# SSFocuser-C-DRV8825.net
KiCad netlist of a schematic drawn in Altium Designer
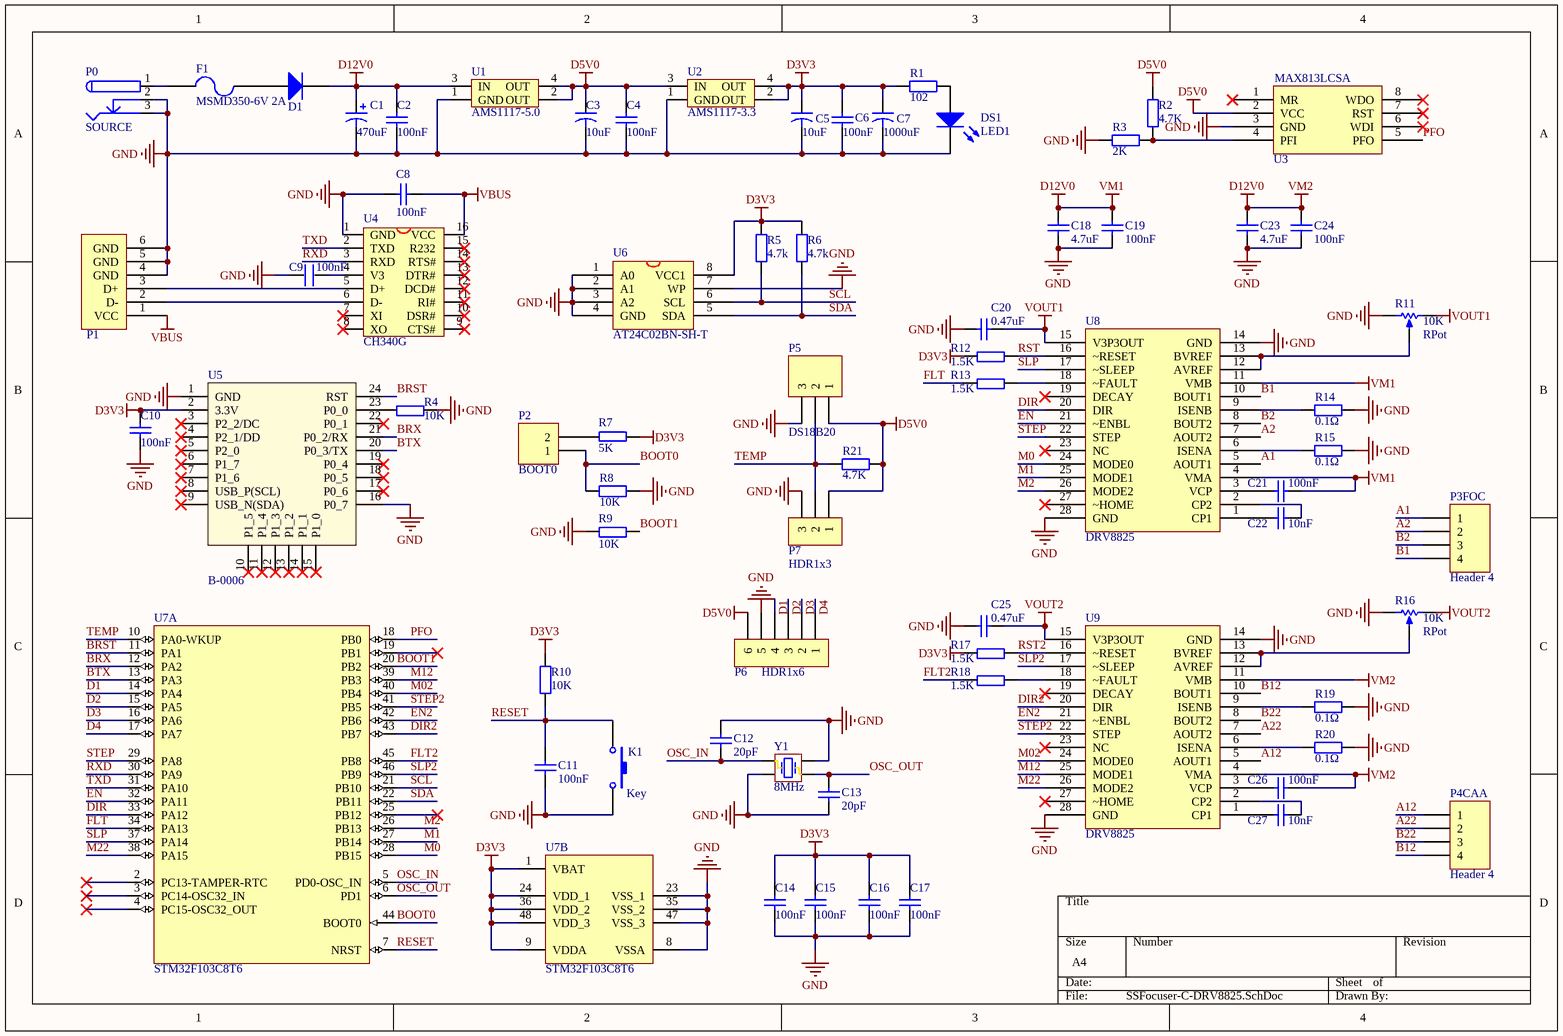
[diagram p0: SSFocuser-C-DRV8825.SchDoc]

(export (version "E")
  (design (tool "Eeschema 10.0.6"))
  (components
    (comp (ref "C1")
      (value "470uF")
      (footprint "16V/470U(CD10X10D5)")
      (description "470UF      16V      CD10X10D5")
      (libsource (lib "平台原理图symbol图库V1.0") (part "C470UF016S"))
    )
    (comp (ref "C2")
      (value "100nF")
      (footprint "0603C")
      (description "Capacitor")
      (fields (field (name "PUBLISHER") "Altium Limited"))
      (libsource (lib "Crazy_PCB") (part "Cap"))
    )
    (comp (ref "C3")
      (value "10uF")
      (footprint "3216")
      (fields (field (name "VAULE") "10uF"))
      (libsource (lib "Crazy_PCB") (part "CAP2"))
    )
    (comp (ref "C4")
      (value "100nF")
      (footprint "0603C")
      (description "Capacitor")
      (fields (field (name "PUBLISHER") "Altium Limited"))
      (libsource (lib "Crazy_PCB") (part "Cap"))
    )
    (comp (ref "C5")
      (value "10uF")
      (footprint "3216")
      (fields (field (name "VAULE") "10uF"))
      (libsource (lib "Crazy_PCB") (part "CAP2"))
    )
    (comp (ref "C6")
      (value "100nF")
      (footprint "0603C")
      (description "Capacitor")
      (fields (field (name "PUBLISHER") "Altium Limited"))
      (libsource (lib "Crazy_PCB") (part "Cap"))
    )
    (comp (ref "C7")
      (value "1000uF")
      (footprint "16V/470U(CD10X10D5)")
      (fields (field (name "VAULE") "1000uF"))
      (libsource (lib "Crazy_PCB") (part "CAP2"))
    )
    (comp (ref "C8")
      (value "100nF")
      (footprint "0603C")
      (description "Capacitor")
      (fields (field (name "PUBLISHER") "Altium Limited"))
      (libsource (lib "Crazy_PCB") (part "Cap"))
    )
    (comp (ref "C9")
      (value "100nF")
      (footprint "0603C")
      (libsource (lib "WarShip V3 STM32103封装库") (part "C"))
    )
    (comp (ref "C10")
      (value "100nF")
      (footprint "0603C")
      (description "Capacitor")
      (fields (field (name "PUBLISHER") "Altium Limited"))
      (libsource (lib "Crazy_PCB") (part "Cap"))
    )
    (comp (ref "C11")
      (value "100nF")
      (footprint "0603C")
      (description "Capacitor")
      (fields (field (name "PUBLISHER") "Altium Limited"))
      (libsource (lib "Crazy_PCB") (part "Cap"))
    )
    (comp (ref "C12")
      (value "20pF")
      (footprint "0603C")
      (description "Capacitor")
      (fields (field (name "PUBLISHER") "Altium Limited"))
      (libsource (lib "JL_SCH") (part "Cap"))
    )
    (comp (ref "C13")
      (value "20pF")
      (footprint "0603C")
      (description "Capacitor")
      (fields (field (name "PUBLISHER") "Altium Limited"))
      (libsource (lib "JL_SCH") (part "Cap"))
    )
    (comp (ref "C14")
      (value "100nF")
      (footprint "0603C")
      (description "Capacitor")
      (fields (field (name "PUBLISHER") "Altium Limited"))
      (libsource (lib "Crazy_PCB") (part "Cap"))
    )
    (comp (ref "C15")
      (value "100nF")
      (footprint "0603C")
      (description "Capacitor")
      (fields (field (name "PUBLISHER") "Altium Limited"))
      (libsource (lib "Crazy_PCB") (part "Cap"))
    )
    (comp (ref "C16")
      (value "100nF")
      (footprint "0603C")
      (description "Capacitor")
      (fields (field (name "PUBLISHER") "Altium Limited"))
      (libsource (lib "Crazy_PCB") (part "Cap"))
    )
    (comp (ref "C17")
      (value "100nF")
      (footprint "0603C")
      (description "Capacitor")
      (fields (field (name "PUBLISHER") "Altium Limited"))
      (libsource (lib "Crazy_PCB") (part "Cap"))
    )
    (comp (ref "C18")
      (value "4.7uF")
      (footprint "1206C")
      (description "Capacitor")
      (fields (field (name "PUBLISHER") "Altium Limited"))
      (libsource (lib "Crazy_PCB") (part "Cap"))
    )
    (comp (ref "C19")
      (value "100nF")
      (footprint "0603C")
      (description "Capacitor")
      (fields (field (name "PUBLISHER") "Altium Limited"))
      (libsource (lib "Crazy_PCB") (part "Cap"))
    )
    (comp (ref "C20")
      (value "0.47uF")
      (footprint "0603C")
      (description "Capacitor")
      (fields (field (name "PUBLISHER") "Altium Limited"))
      (libsource (lib "Crazy_PCB") (part "Cap"))
    )
    (comp (ref "C21")
      (value "100nF")
      (footprint "0603C")
      (description "Capacitor")
      (fields (field (name "PUBLISHER") "Altium Limited"))
      (libsource (lib "Crazy_PCB") (part "Cap"))
    )
    (comp (ref "C22")
      (value "10nF")
      (footprint "0603C")
      (description "Capacitor")
      (fields (field (name "PUBLISHER") "Altium Limited"))
      (libsource (lib "Crazy_PCB") (part "Cap"))
    )
    (comp (ref "C23")
      (value "4.7uF")
      (footprint "1206C")
      (description "Capacitor")
      (fields (field (name "PUBLISHER") "Altium Limited"))
      (libsource (lib "Crazy_PCB") (part "Cap"))
    )
    (comp (ref "C24")
      (value "100nF")
      (footprint "0603C")
      (description "Capacitor")
      (fields (field (name "PUBLISHER") "Altium Limited"))
      (libsource (lib "Crazy_PCB") (part "Cap"))
    )
    (comp (ref "C25")
      (value "0.47uF")
      (footprint "0603C")
      (description "Capacitor")
      (fields (field (name "PUBLISHER") "Altium Limited"))
      (libsource (lib "Crazy_PCB") (part "Cap"))
    )
    (comp (ref "C26")
      (value "100nF")
      (footprint "0603C")
      (description "Capacitor")
      (fields (field (name "PUBLISHER") "Altium Limited"))
      (libsource (lib "Crazy_PCB") (part "Cap"))
    )
    (comp (ref "C27")
      (value "10nF")
      (footprint "0603C")
      (description "Capacitor")
      (fields (field (name "PUBLISHER") "Altium Limited"))
      (libsource (lib "Crazy_PCB") (part "Cap"))
    )
    (comp (ref "D1")
      (value "M7")
      (footprint "DO-214AC")
      (description "High Conductance Fast Diode")
      (fields (field (name "PUBLISHER") "Altium Limited"))
      (libsource (lib "Crazy_PCB") (part "Diode"))
    )
    (comp (ref "DS1")
      (value "LED1")
      (footprint "0805D")
      (description "Typical RED, GREEN, YELLOW, AMBER GaAs LED")
      (fields (field (name "PUBLISHER") "Altium Limited"))
      (libsource (lib "MiniSTM32 V3.0封装库") (part "LED2"))
    )
    (comp (ref "F1")
      (value "MSMD350-6V 2A")
      (footprint "1812R")
      (description "Fuse")
      (libsource (lib "JL_SCH") (part "FUSE2"))
    )
    (comp (ref "K1")
      (value "Key")
      (footprint "SW-4*6")
      (description "Switch")
      (fields (field (name "PUBLISHER") "Altium Limited"))
      (libsource (lib "Crazy_PCB") (part "KEY2"))
    )
    (comp (ref "P0")
      (value "SOURCE")
      (footprint "DC_5.5MM")
      (fields (field (name "PUBLISHER") "Altium Limited"))
      (libsource (lib "Crazy_PCB") (part "SOURCE"))
    )
    (comp (ref "P1") (value "USB-B") (footprint "USB-B") (libsource (lib "DX") (part "USB-B")))
    (comp (ref "P2")
      (value "BOOT0")
      (footprint "HDR1X2")
      (description "Header, 2-Pin")
      (fields (field (name "PUBLISHER") "Altium Limited"))
      (libsource (lib "Miscellaneous Connectors") (part "MHDR1X2"))
    )
    (comp (ref "P3FOC")
      (value "Header 4")
      (footprint "XH_4_V")
      (description "Header, 4-Pin")
      (fields (field (name "PUBLISHER") "Altium Limited"))
      (libsource (lib "Miscellaneous Connectors") (part "Header 4"))
    )
    (comp (ref "P4CAA")
      (value "Header 4")
      (footprint "XH_4_V")
      (description "Header, 4-Pin")
      (fields (field (name "PUBLISHER") "Altium Limited"))
      (libsource (lib "Miscellaneous Connectors") (part "Header 4"))
    )
    (comp (ref "P5")
      (value "DS18B20")
      (footprint "TO-92B")
      (description "Header, 3-Pin")
      (fields (field (name "PUBLISHER") "Altium Limited"))
      (libsource (lib "Miscellaneous Connectors") (part "Header 3"))
    )
    (comp (ref "P6")
      (value "HDR1x6")
      (footprint "PIN-6-2.54-1.0")
      (description "Connector")
      (libsource (lib "General") (part "HDR1x6"))
    )
    (comp (ref "P7")
      (value "HDR1x3")
      (footprint "PIN-3-2.54-1.0")
      (description "Connector")
      (libsource (lib "General") (part "HDR1x3"))
    )
    (comp (ref "R1")
      (value "102")
      (footprint "0603R")
      (description "Resistor")
      (fields (field (name "PUBLISHER") "Altium Limited"))
      (libsource (lib "") (part "RES_1"))
    )
    (comp (ref "R2")
      (value "4.7K")
      (footprint "0603R")
      (description "Resistor")
      (fields (field (name "PUBLISHER") "Altium Limited"))
      (libsource (lib "") (part "RES_2"))
    )
    (comp (ref "R3")
      (value "2K")
      (footprint "0603R")
      (description "Resistor")
      (fields (field (name "PUBLISHER") "Altium Limited"))
      (libsource (lib "") (part "RES_1"))
    )
    (comp (ref "R4") (value "10K") (footprint "0603R") (libsource (lib "WarShip V3 STM32103封装库") (part "R")))
    (comp (ref "R5")
      (value "4.7k")
      (footprint "0603R")
      (description "Resistor")
      (fields (field (name "PUBLISHER") "Altium Limited"))
      (libsource (lib "") (part "RES_2"))
    )
    (comp (ref "R6")
      (value "4.7k")
      (footprint "0603R")
      (description "Resistor")
      (fields (field (name "PUBLISHER") "Altium Limited"))
      (libsource (lib "") (part "RES_2"))
    )
    (comp (ref "R7") (value "5K") (footprint "0603R") (libsource (lib "WarShip V3 STM32103封装库") (part "R")))
    (comp (ref "R8")
      (value "10K")
      (footprint "0603R")
      (description "Resistor")
      (fields (field (name "PUBLISHER") "Altium Limited"))
      (libsource (lib "Crazy_PCB") (part "RES"))
    )
    (comp (ref "R9") (value "10K") (footprint "0603R") (libsource (lib "WarShip V3 STM32103封装库") (part "R")))
    (comp (ref "R10")
      (value "10K")
      (footprint "0603R")
      (description "Resistor")
      (fields (field (name "PUBLISHER") "Altium Limited"))
      (libsource (lib "") (part "RES_2"))
    )
    (comp (ref "R11")
      (value "RPot")
      (footprint "VR_SMD")
      (description "Potentiometer")
      (fields (field (name "ALTIUM_VALUE") "10K") (field (name "PUBLISHER") "Altium Limited"))
      (libsource (lib "Miscellaneous Devices") (part "RPot"))
    )
    (comp (ref "R12")
      (value "1.5K")
      (footprint "0603R")
      (libsource (lib "WarShip V3 STM32103封装库") (part "R"))
    )
    (comp (ref "R13")
      (value "1.5K")
      (footprint "0603R")
      (libsource (lib "WarShip V3 STM32103封装库") (part "R"))
    )
    (comp (ref "R14")
      (value "0.1Ω")
      (footprint "1206R")
      (description "Resistor")
      (fields (field (name "PUBLISHER") "Altium Limited"))
      (libsource (lib "") (part "RES_1"))
    )
    (comp (ref "R15")
      (value "0.1Ω")
      (footprint "1206R")
      (description "Resistor")
      (fields (field (name "PUBLISHER") "Altium Limited"))
      (libsource (lib "") (part "RES_1"))
    )
    (comp (ref "R16")
      (value "RPot")
      (footprint "VR_SMD")
      (description "Potentiometer")
      (fields (field (name "ALTIUM_VALUE") "10K") (field (name "PUBLISHER") "Altium Limited"))
      (libsource (lib "Miscellaneous Devices") (part "RPot"))
    )
    (comp (ref "R17")
      (value "1.5K")
      (footprint "0603R")
      (libsource (lib "WarShip V3 STM32103封装库") (part "R"))
    )
    (comp (ref "R18")
      (value "1.5K")
      (footprint "0603R")
      (libsource (lib "WarShip V3 STM32103封装库") (part "R"))
    )
    (comp (ref "R19")
      (value "0.1Ω")
      (footprint "1206R")
      (description "Resistor")
      (fields (field (name "PUBLISHER") "Altium Limited"))
      (libsource (lib "") (part "RES_1"))
    )
    (comp (ref "R20")
      (value "0.1Ω")
      (footprint "1206R")
      (description "Resistor")
      (fields (field (name "PUBLISHER") "Altium Limited"))
      (libsource (lib "") (part "RES_1"))
    )
    (comp (ref "R21")
      (value "4.7K")
      (footprint "0603R")
      (description "Resistor")
      (fields (field (name "PUBLISHER") "Altium Limited"))
      (libsource (lib "Crazy_PCB") (part "RES"))
    )
    (comp (ref "U1")
      (value "AMS1117-5.0")
      (footprint "SOT223")
      (libsource (lib "MiniSTM32 V3.0封装库") (part "AMS1117"))
    )
    (comp (ref "U2")
      (value "AMS1117-3.3")
      (footprint "SOT223")
      (libsource (lib "MiniSTM32 V3.0封装库") (part "AMS1117"))
    )
    (comp (ref "U3") (value "MAX813LCSA") (footprint "SOP-8") (libsource (lib "DX") (part "MAX813L")))
    (comp (ref "U4")
      (value "CH340G")
      (footprint "SO-16")
      (description "USB2UART")
      (libsource (lib "WarShip V3 STM32103封装库") (part "CH340G"))
    )
    (comp (ref "U5") (value "B-0006") (footprint "B-0006") (libsource (lib "B-0006") (part "B-0006")))
    (comp (ref "U6")
      (value "AT24C02BN-SH-T")
      (footprint "SOP-8")
      (libsource (lib "MiniSTM32 V3.0封装库") (part "24C256"))
    )
    (comp (ref "U7")
      (value "STM32F103C8T6")
      (footprint "LQFP48_N")
      (libsource (lib "STMicroelectronics STM32 F1") (part "STM32F103C8T6"))
    )
    (comp (ref "U8") (value "DRV8825") (footprint "HTSSOP") (libsource (lib "MySchlib") (part "DRV8825")))
    (comp (ref "U9") (value "DRV8825") (footprint "HTSSOP") (libsource (lib "MySchlib") (part "DRV8825")))
    (comp (ref "Y1")
      (value "8MHz")
      (footprint "X3225")
      (description "Crystal Oscillator")
      (fields (field (name "PUBLISHER") "Altium Limited"))
      (libsource (lib "JL_SCH") (part "XTAL_1"))
    )
  )
  (nets
    (net (code "1") (name "/A1") (class "Default")
      (node (ref "P3FOC") (pin "1") (pinfunction "1_1") (pintype "passive"))
      (node (ref "U8") (pin "5") (pinfunction "AOUT1_5") (pintype "passive"))
    )
    (net (code "2") (name "/A2") (class "Default")
      (node (ref "P3FOC") (pin "2") (pinfunction "2_2") (pintype "passive"))
      (node (ref "U8") (pin "7") (pinfunction "AOUT2_7") (pintype "passive"))
    )
    (net (code "3") (name "/A12") (class "Default")
      (node (ref "P4CAA") (pin "1") (pinfunction "1_1") (pintype "passive"))
      (node (ref "U9") (pin "5") (pinfunction "AOUT1_5") (pintype "passive"))
    )
    (net (code "4") (name "/A22") (class "Default")
      (node (ref "P4CAA") (pin "2") (pinfunction "2_2") (pintype "passive"))
      (node (ref "U9") (pin "7") (pinfunction "AOUT2_7") (pintype "passive"))
    )
    (net (code "5") (name "/B1") (class "Default")
      (node (ref "P3FOC") (pin "4") (pinfunction "4_4") (pintype "passive"))
      (node (ref "U8") (pin "10") (pinfunction "BOUT1_10") (pintype "passive"))
    )
    (net (code "6") (name "/B2") (class "Default")
      (node (ref "P3FOC") (pin "3") (pinfunction "3_3") (pintype "passive"))
      (node (ref "U8") (pin "8") (pinfunction "BOUT2_8") (pintype "passive"))
    )
    (net (code "7") (name "/B12") (class "Default")
      (node (ref "P4CAA") (pin "4") (pinfunction "4_4") (pintype "passive"))
      (node (ref "U9") (pin "10") (pinfunction "BOUT1_10") (pintype "passive"))
    )
    (net (code "8") (name "/B22") (class "Default")
      (node (ref "P4CAA") (pin "3") (pinfunction "3_3") (pintype "passive"))
      (node (ref "U9") (pin "8") (pinfunction "BOUT2_8") (pintype "passive"))
    )
    (net (code "9") (name "/BOOT0") (class "Default")
      (node (ref "P2") (pin "1") (pinfunction "1_1") (pintype "passive"))
      (node (ref "R8") (pin "1") (pinfunction "1_1") (pintype "passive"))
      (node (ref "U7") (pin "44") (pinfunction "BOOT0_44") (pintype "input"))
    )
    (net (code "10") (name "/BOOT1") (class "Default")
      (node (ref "R9") (pin "2") (pintype "passive"))
      (node (ref "U7") (pin "20") (pinfunction "PB2_20") (pintype "bidirectional"))
    )
    (net (code "11") (name "/BRST") (class "Default")
      (node (ref "U5") (pin "24") (pinfunction "RST_24") (pintype "passive"))
      (node (ref "U7") (pin "11") (pinfunction "PA1_11") (pintype "bidirectional"))
    )
    (net (code "12") (name "/BRX") (class "Default")
      (node (ref "U5") (pin "21") (pinfunction "P0_2/RX_21") (pintype "passive"))
      (node (ref "U7") (pin "12") (pinfunction "PA2_12") (pintype "bidirectional"))
    )
    (net (code "13") (name "/BTX") (class "Default")
      (node (ref "U5") (pin "20") (pinfunction "P0_3/TX_20") (pintype "passive"))
      (node (ref "U7") (pin "13") (pinfunction "PA3_13") (pintype "bidirectional"))
    )
    (net (code "14") (name "/D1") (class "Default")
      (node (ref "P6") (pin "4") (pinfunction "4_4") (pintype "passive"))
      (node (ref "U7") (pin "14") (pinfunction "PA4_14") (pintype "bidirectional"))
    )
    (net (code "15") (name "/D2") (class "Default")
      (node (ref "P6") (pin "3") (pinfunction "3_3") (pintype "passive"))
      (node (ref "U7") (pin "15") (pinfunction "PA5_15") (pintype "bidirectional"))
    )
    (net (code "16") (name "/D3") (class "Default")
      (node (ref "P6") (pin "2") (pinfunction "2_2") (pintype "passive"))
      (node (ref "U7") (pin "16") (pinfunction "PA6_16") (pintype "bidirectional"))
    )
    (net (code "17") (name "/D4") (class "Default")
      (node (ref "P6") (pin "1") (pinfunction "1_1") (pintype "passive"))
      (node (ref "U7") (pin "17") (pinfunction "PA7_17") (pintype "bidirectional"))
    )
    (net (code "18") (name "/DIR") (class "Default")
      (node (ref "U7") (pin "33") (pinfunction "PA12_33") (pintype "bidirectional"))
      (node (ref "U8") (pin "20") (pinfunction "DIR_20") (pintype "passive"))
    )
    (net (code "19") (name "/DIR2") (class "Default")
      (node (ref "U7") (pin "43") (pinfunction "PB7_43") (pintype "bidirectional"))
      (node (ref "U9") (pin "20") (pinfunction "DIR_20") (pintype "passive"))
    )
    (net (code "20") (name "/EN") (class "Default")
      (node (ref "U7") (pin "32") (pinfunction "PA11_32") (pintype "bidirectional"))
      (node (ref "U8") (pin "21") (pinfunction "~ENBL_21") (pintype "passive"))
    )
    (net (code "21") (name "/EN2") (class "Default")
      (node (ref "U7") (pin "42") (pinfunction "PB6_42") (pintype "bidirectional"))
      (node (ref "U9") (pin "21") (pinfunction "~ENBL_21") (pintype "passive"))
    )
    (net (code "22") (name "/FLT") (class "Default")
      (node (ref "R13") (pin "1") (pintype "passive"))
      (node (ref "U7") (pin "34") (pinfunction "PA13_34") (pintype "bidirectional"))
    )
    (net (code "23") (name "/FLT2") (class "Default")
      (node (ref "R18") (pin "1") (pintype "passive"))
      (node (ref "U7") (pin "45") (pinfunction "PB8_45") (pintype "bidirectional"))
    )
    (net (code "24") (name "/M0") (class "Default")
      (node (ref "U7") (pin "28") (pinfunction "PB15_28") (pintype "bidirectional"))
      (node (ref "U8") (pin "24") (pinfunction "MODE0_24") (pintype "passive"))
    )
    (net (code "25") (name "/M1") (class "Default")
      (node (ref "U7") (pin "27") (pinfunction "PB14_27") (pintype "bidirectional"))
      (node (ref "U8") (pin "25") (pinfunction "MODE1_25") (pintype "passive"))
    )
    (net (code "26") (name "/M02") (class "Default")
      (node (ref "U7") (pin "40") (pinfunction "PB4_40") (pintype "bidirectional"))
      (node (ref "U9") (pin "24") (pinfunction "MODE0_24") (pintype "passive"))
    )
    (net (code "27") (name "/M2") (class "Default")
      (node (ref "U7") (pin "26") (pinfunction "PB13_26") (pintype "bidirectional"))
      (node (ref "U8") (pin "26") (pinfunction "MODE2_26") (pintype "passive"))
    )
    (net (code "28") (name "/M12") (class "Default")
      (node (ref "U7") (pin "39") (pinfunction "PB3_39") (pintype "bidirectional"))
      (node (ref "U9") (pin "25") (pinfunction "MODE1_25") (pintype "passive"))
    )
    (net (code "29") (name "/M22") (class "Default")
      (node (ref "U7") (pin "38") (pinfunction "PA15_38") (pintype "bidirectional"))
      (node (ref "U9") (pin "26") (pinfunction "MODE2_26") (pintype "passive"))
    )
    (net (code "30") (name "/OSC_IN") (class "Default")
      (node (ref "C12") (pin "1") (pinfunction "1_1") (pintype "passive"))
      (node (ref "U7") (pin "5") (pinfunction "PD0-OSC_IN_5") (pintype "bidirectional"))
      (node (ref "Y1") (pin "1") (pinfunction "OSC1_1") (pintype "passive"))
    )
    (net (code "31") (name "/OSC_OUT") (class "Default")
      (node (ref "C13") (pin "1") (pinfunction "1_1") (pintype "passive"))
      (node (ref "U7") (pin "6") (pinfunction "PD1_6") (pintype "bidirectional"))
      (node (ref "Y1") (pin "3") (pinfunction "OSC2_3") (pintype "passive"))
    )
    (net (code "32") (name "/PFO") (class "Default")
      (node (ref "U3") (pin "5") (pinfunction "PFO_5") (pintype "passive"))
      (node (ref "U7") (pin "18") (pinfunction "PB0_18") (pintype "bidirectional"))
    )
    (net (code "33") (name "/RESET") (class "Default")
      (node (ref "C11") (pin "2") (pinfunction "2_2") (pintype "passive"))
      (node (ref "K1") (pin "1") (pinfunction "1_1") (pintype "passive"))
      (node (ref "R10") (pin "1") (pinfunction "1_1") (pintype "passive"))
      (node (ref "U7") (pin "7") (pinfunction "NRST_7") (pintype "bidirectional"))
    )
    (net (code "34") (name "/RST") (class "Default")
      (node (ref "R12") (pin "2") (pintype "passive"))
      (node (ref "U8") (pin "16") (pinfunction "~RESET_16") (pintype "passive"))
    )
    (net (code "35") (name "/RST2") (class "Default")
      (node (ref "R17") (pin "2") (pintype "passive"))
      (node (ref "U9") (pin "16") (pinfunction "~RESET_16") (pintype "passive"))
    )
    (net (code "36") (name "/RXD") (class "Default")
      (node (ref "U4") (pin "3") (pinfunction "RXD_3") (pintype "passive"))
      (node (ref "U7") (pin "30") (pinfunction "PA9_30") (pintype "bidirectional"))
    )
    (net (code "37") (name "/SCL") (class "Default")
      (node (ref "R5") (pin "1") (pinfunction "1_1") (pintype "passive"))
      (node (ref "U6") (pin "6") (pinfunction "SCL_6") (pintype "passive"))
      (node (ref "U7") (pin "21") (pinfunction "PB10_21") (pintype "bidirectional"))
    )
    (net (code "38") (name "/SDA") (class "Default")
      (node (ref "R6") (pin "1") (pinfunction "1_1") (pintype "passive"))
      (node (ref "U6") (pin "5") (pinfunction "SDA_5") (pintype "passive"))
      (node (ref "U7") (pin "22") (pinfunction "PB11_22") (pintype "bidirectional"))
    )
    (net (code "39") (name "/SLP") (class "Default")
      (node (ref "U7") (pin "37") (pinfunction "PA14_37") (pintype "bidirectional"))
      (node (ref "U8") (pin "17") (pinfunction "~SLEEP_17") (pintype "passive"))
    )
    (net (code "40") (name "/SLP2") (class "Default")
      (node (ref "U7") (pin "46") (pinfunction "PB9_46") (pintype "bidirectional"))
      (node (ref "U9") (pin "17") (pinfunction "~SLEEP_17") (pintype "passive"))
    )
    (net (code "41") (name "/STEP") (class "Default")
      (node (ref "U7") (pin "29") (pinfunction "PA8_29") (pintype "bidirectional"))
      (node (ref "U8") (pin "22") (pinfunction "STEP_22") (pintype "passive"))
    )
    (net (code "42") (name "/STEP2") (class "Default")
      (node (ref "U7") (pin "41") (pinfunction "PB5_41") (pintype "bidirectional"))
      (node (ref "U9") (pin "22") (pinfunction "STEP_22") (pintype "passive"))
    )
    (net (code "43") (name "/TEMP") (class "Default")
      (node (ref "P5") (pin "2") (pinfunction "2_2") (pintype "passive"))
      (node (ref "P7") (pin "2") (pinfunction "2_2") (pintype "passive"))
      (node (ref "R21") (pin "1") (pinfunction "1_1") (pintype "passive"))
      (node (ref "U7") (pin "10") (pinfunction "PA0-WKUP_10") (pintype "bidirectional"))
    )
    (net (code "44") (name "/TXD") (class "Default")
      (node (ref "U4") (pin "2") (pinfunction "TXD_2") (pintype "passive"))
      (node (ref "U7") (pin "31") (pinfunction "PA10_31") (pintype "bidirectional"))
    )
    (net (code "45") (name "D3V3") (class "Default")
      (node (ref "C10") (pin "2") (pinfunction "2_2") (pintype "passive"))
      (node (ref "C14") (pin "2") (pinfunction "2_2") (pintype "passive"))
      (node (ref "C15") (pin "2") (pinfunction "2_2") (pintype "passive"))
      (node (ref "C16") (pin "2") (pinfunction "2_2") (pintype "passive"))
      (node (ref "C17") (pin "2") (pinfunction "2_2") (pintype "passive"))
      (node (ref "C5") (pin "1") (pinfunction "1_1") (pintype "passive"))
      (node (ref "C6") (pin "2") (pinfunction "2_2") (pintype "passive"))
      (node (ref "C7") (pin "1") (pinfunction "1_1") (pintype "passive"))
      (node (ref "R1") (pin "2") (pinfunction "2_2") (pintype "passive"))
      (node (ref "R10") (pin "2") (pinfunction "2_2") (pintype "passive"))
      (node (ref "R12") (pin "1") (pintype "passive"))
      (node (ref "R17") (pin "1") (pintype "passive"))
      (node (ref "R5") (pin "2") (pinfunction "2_2") (pintype "passive"))
      (node (ref "R6") (pin "2") (pinfunction "2_2") (pintype "passive"))
      (node (ref "R7") (pin "1") (pintype "passive"))
      (node (ref "U2") (pin "2") (pinfunction "OUT_2") (pintype "passive"))
      (node (ref "U2") (pin "4") (pinfunction "OUT_4") (pintype "passive"))
      (node (ref "U5") (pin "2") (pinfunction "3.3V_2") (pintype "passive"))
      (node (ref "U6") (pin "8") (pinfunction "VCC1_8") (pintype "passive"))
      (node (ref "U7") (pin "1") (pinfunction "VBAT_1") (pintype "power_in"))
      (node (ref "U7") (pin "24") (pinfunction "VDD_1_24") (pintype "power_in"))
      (node (ref "U7") (pin "36") (pinfunction "VDD_2_36") (pintype "power_in"))
      (node (ref "U7") (pin "48") (pinfunction "VDD_3_48") (pintype "power_in"))
      (node (ref "U7") (pin "9") (pinfunction "VDDA_9") (pintype "power_in"))
    )
    (net (code "46") (name "D5V0") (class "Default")
      (node (ref "C3") (pin "1") (pinfunction "1_1") (pintype "passive"))
      (node (ref "C4") (pin "2") (pinfunction "2_2") (pintype "passive"))
      (node (ref "P5") (pin "1") (pinfunction "1_1") (pintype "passive"))
      (node (ref "P6") (pin "6") (pinfunction "6_6") (pintype "passive"))
      (node (ref "P7") (pin "1") (pinfunction "1_1") (pintype "passive"))
      (node (ref "R2") (pin "2") (pinfunction "2_2") (pintype "passive"))
      (node (ref "R21") (pin "2") (pinfunction "2_2") (pintype "passive"))
      (node (ref "U1") (pin "2") (pinfunction "OUT_2") (pintype "passive"))
      (node (ref "U1") (pin "4") (pinfunction "OUT_4") (pintype "passive"))
      (node (ref "U2") (pin "3") (pinfunction "IN_3") (pintype "passive"))
      (node (ref "U3") (pin "2") (pinfunction "VCC_2") (pintype "passive"))
    )
    (net (code "47") (name "D12V0") (class "Default")
      (node (ref "C1") (pin "1") (pinfunction "1_1") (pintype "passive"))
      (node (ref "C18") (pin "1") (pinfunction "1_1") (pintype "passive"))
      (node (ref "C19") (pin "1") (pinfunction "1_1") (pintype "passive"))
      (node (ref "C2") (pin "2") (pinfunction "2_2") (pintype "passive"))
      (node (ref "C21") (pin "1") (pinfunction "1_1") (pintype "passive"))
      (node (ref "C23") (pin "1") (pinfunction "1_1") (pintype "passive"))
      (node (ref "C24") (pin "1") (pinfunction "1_1") (pintype "passive"))
      (node (ref "C26") (pin "1") (pinfunction "1_1") (pintype "passive"))
      (node (ref "D1") (pin "2") (pinfunction "K_2") (pintype "passive"))
      (node (ref "U1") (pin "3") (pinfunction "IN_3") (pintype "passive"))
      (node (ref "U8") (pin "11") (pinfunction "VMB_11") (pintype "passive"))
      (node (ref "U8") (pin "4") (pinfunction "VMA_4") (pintype "passive"))
      (node (ref "U9") (pin "11") (pinfunction "VMB_11") (pintype "passive"))
      (node (ref "U9") (pin "4") (pinfunction "VMA_4") (pintype "passive"))
    )
    (net (code "48") (name "GND") (class "Default")
      (node (ref "C1") (pin "2") (pinfunction "2_2") (pintype "passive"))
      (node (ref "C10") (pin "1") (pinfunction "1_1") (pintype "passive"))
      (node (ref "C11") (pin "1") (pinfunction "1_1") (pintype "passive"))
      (node (ref "C12") (pin "2") (pinfunction "2_2") (pintype "passive"))
      (node (ref "C13") (pin "2") (pinfunction "2_2") (pintype "passive"))
      (node (ref "C14") (pin "1") (pinfunction "1_1") (pintype "passive"))
      (node (ref "C15") (pin "1") (pinfunction "1_1") (pintype "passive"))
      (node (ref "C16") (pin "1") (pinfunction "1_1") (pintype "passive"))
      (node (ref "C17") (pin "1") (pinfunction "1_1") (pintype "passive"))
      (node (ref "C18") (pin "2") (pinfunction "2_2") (pintype "passive"))
      (node (ref "C19") (pin "2") (pinfunction "2_2") (pintype "passive"))
      (node (ref "C2") (pin "1") (pinfunction "1_1") (pintype "passive"))
      (node (ref "C20") (pin "1") (pinfunction "1_1") (pintype "passive"))
      (node (ref "C23") (pin "2") (pinfunction "2_2") (pintype "passive"))
      (node (ref "C24") (pin "2") (pinfunction "2_2") (pintype "passive"))
      (node (ref "C25") (pin "1") (pinfunction "1_1") (pintype "passive"))
      (node (ref "C3") (pin "2") (pinfunction "2_2") (pintype "passive"))
      (node (ref "C4") (pin "1") (pinfunction "1_1") (pintype "passive"))
      (node (ref "C5") (pin "2") (pinfunction "2_2") (pintype "passive"))
      (node (ref "C6") (pin "1") (pinfunction "1_1") (pintype "passive"))
      (node (ref "C7") (pin "2") (pinfunction "2_2") (pintype "passive"))
      (node (ref "C8") (pin "1") (pinfunction "1_1") (pintype "passive"))
      (node (ref "C9") (pin "1") (pintype "passive"))
      (node (ref "DS1") (pin "2") (pinfunction "K_2") (pintype "passive"))
      (node (ref "K1") (pin "2") (pinfunction "2_2") (pintype "passive"))
      (node (ref "P0") (pin "2") (pinfunction "2_2") (pintype "power_in"))
      (node (ref "P0") (pin "3") (pinfunction "3_3") (pintype "power_in"))
      (node (ref "P1") (pin "4") (pinfunction "GND_4") (pintype "passive"))
      (node (ref "P1") (pin "5") (pinfunction "GND_5") (pintype "passive"))
      (node (ref "P1") (pin "6") (pinfunction "GND_6") (pintype "passive"))
      (node (ref "P5") (pin "3") (pinfunction "3_3") (pintype "passive"))
      (node (ref "P6") (pin "5") (pinfunction "5_5") (pintype "passive"))
      (node (ref "P7") (pin "3") (pinfunction "3_3") (pintype "passive"))
      (node (ref "R11") (pin "1") (pinfunction "TOP_1") (pintype "passive"))
      (node (ref "R14") (pin "1") (pinfunction "1_1") (pintype "passive"))
      (node (ref "R15") (pin "1") (pinfunction "1_1") (pintype "passive"))
      (node (ref "R16") (pin "1") (pinfunction "TOP_1") (pintype "passive"))
      (node (ref "R19") (pin "1") (pinfunction "1_1") (pintype "passive"))
      (node (ref "R20") (pin "1") (pinfunction "1_1") (pintype "passive"))
      (node (ref "R3") (pin "2") (pinfunction "2_2") (pintype "passive"))
      (node (ref "R4") (pin "2") (pintype "passive"))
      (node (ref "R8") (pin "2") (pinfunction "2_2") (pintype "passive"))
      (node (ref "R9") (pin "1") (pintype "passive"))
      (node (ref "U1") (pin "1") (pinfunction "GND_1") (pintype "passive"))
      (node (ref "U2") (pin "1") (pinfunction "GND_1") (pintype "passive"))
      (node (ref "U3") (pin "3") (pinfunction "GND_3") (pintype "passive"))
      (node (ref "U4") (pin "1") (pinfunction "GND_1") (pintype "passive"))
      (node (ref "U5") (pin "1") (pinfunction "GND_1") (pintype "passive"))
      (node (ref "U5") (pin "16") (pinfunction "P0_7_16") (pintype "passive"))
      (node (ref "U6") (pin "1") (pinfunction "A0_1") (pintype "passive"))
      (node (ref "U6") (pin "2") (pinfunction "A1_2") (pintype "passive"))
      (node (ref "U6") (pin "3") (pinfunction "A2_3") (pintype "passive"))
      (node (ref "U6") (pin "4") (pinfunction "GND_4") (pintype "passive"))
      (node (ref "U6") (pin "7") (pinfunction "WP_7") (pintype "passive"))
      (node (ref "U7") (pin "23") (pinfunction "VSS_1_23") (pintype "power_in"))
      (node (ref "U7") (pin "35") (pinfunction "VSS_2_35") (pintype "power_in"))
      (node (ref "U7") (pin "47") (pinfunction "VSS_3_47") (pintype "power_in"))
      (node (ref "U7") (pin "8") (pinfunction "VSSA_8") (pintype "power_in"))
      (node (ref "U8") (pin "14") (pinfunction "GND_14") (pintype "passive"))
      (node (ref "U8") (pin "28") (pinfunction "GND_28") (pintype "passive"))
      (node (ref "U9") (pin "14") (pinfunction "GND_14") (pintype "passive"))
      (node (ref "U9") (pin "28") (pinfunction "GND_28") (pintype "passive"))
      (node (ref "Y1") (pin "2") (pinfunction "NA_2") (pintype "passive"))
      (node (ref "Y1") (pin "4") (pinfunction "NA_4") (pintype "passive"))
    )
    (net (code "49") (name "Net-(D1-A)") (class "Default")
      (node (ref "D1") (pin "1") (pinfunction "A_1") (pintype "passive"))
      (node (ref "F1") (pin "1") (pinfunction "1_1") (pintype "passive"))
    )
    (net (code "50") (name "Net-(DS1-A)") (class "Default")
      (node (ref "DS1") (pin "1") (pinfunction "A_1") (pintype "passive"))
      (node (ref "R1") (pin "1") (pinfunction "1_1") (pintype "passive"))
    )
    (net (code "51") (name "Net-(F1-Pad2)") (class "Default")
      (node (ref "F1") (pin "2") (pinfunction "2_2") (pintype "passive"))
      (node (ref "P0") (pin "1") (pinfunction "1_1") (pintype "power_in"))
    )
    (net (code "52") (name "Net-(P1-D+)") (class "Default")
      (node (ref "P1") (pin "3") (pinfunction "D+_3") (pintype "passive"))
      (node (ref "U4") (pin "5") (pinfunction "D+_5") (pintype "passive"))
    )
    (net (code "53") (name "Net-(P1-D-)") (class "Default")
      (node (ref "P1") (pin "2") (pinfunction "D-_2") (pintype "passive"))
      (node (ref "U4") (pin "6") (pinfunction "D-_6") (pintype "passive"))
    )
    (net (code "54") (name "Net-(P2-Pad2)") (class "Default")
      (node (ref "P2") (pin "2") (pinfunction "2_2") (pintype "passive"))
      (node (ref "R7") (pin "2") (pintype "passive"))
    )
    (net (code "55") (name "Net-(R11-TAP)") (class "Default")
      (node (ref "R11") (pin "3") (pinfunction "TAP_3") (pintype "passive"))
      (node (ref "U8") (pin "12") (pinfunction "AVREF_12") (pintype "passive"))
      (node (ref "U8") (pin "13") (pinfunction "BVREF_13") (pintype "passive"))
    )
    (net (code "56") (name "Net-(R16-TAP)") (class "Default")
      (node (ref "R16") (pin "3") (pinfunction "TAP_3") (pintype "passive"))
      (node (ref "U9") (pin "12") (pinfunction "AVREF_12") (pintype "passive"))
      (node (ref "U9") (pin "13") (pinfunction "BVREF_13") (pintype "passive"))
    )
    (net (code "57") (name "Net-(U3-PFI)") (class "Default")
      (node (ref "R2") (pin "1") (pinfunction "1_1") (pintype "passive"))
      (node (ref "R3") (pin "1") (pinfunction "1_1") (pintype "passive"))
      (node (ref "U3") (pin "4") (pinfunction "PFI_4") (pintype "passive"))
    )
    (net (code "58") (name "Net-(U4-V3)") (class "Default")
      (node (ref "C9") (pin "2") (pintype "passive"))
      (node (ref "U4") (pin "4") (pinfunction "V3_4") (pintype "passive"))
    )
    (net (code "59") (name "Net-(U5-P0_0)") (class "Default")
      (node (ref "R4") (pin "1") (pintype "passive"))
      (node (ref "U5") (pin "23") (pinfunction "P0_0_23") (pintype "passive"))
    )
    (net (code "60") (name "Net-(U8-CP1)") (class "Default")
      (node (ref "C22") (pin "2") (pinfunction "2_2") (pintype "passive"))
      (node (ref "U8") (pin "1") (pinfunction "CP1_1") (pintype "passive"))
    )
    (net (code "61") (name "Net-(U8-CP2)") (class "Default")
      (node (ref "C22") (pin "1") (pinfunction "1_1") (pintype "passive"))
      (node (ref "U8") (pin "2") (pinfunction "CP2_2") (pintype "passive"))
    )
    (net (code "62") (name "Net-(U8-ISENA)") (class "Default")
      (node (ref "R15") (pin "2") (pinfunction "2_2") (pintype "passive"))
      (node (ref "U8") (pin "6") (pinfunction "ISENA_6") (pintype "passive"))
    )
    (net (code "63") (name "Net-(U8-ISENB)") (class "Default")
      (node (ref "R14") (pin "2") (pinfunction "2_2") (pintype "passive"))
      (node (ref "U8") (pin "9") (pinfunction "ISENB_9") (pintype "passive"))
    )
    (net (code "64") (name "Net-(U8-VCP)") (class "Default")
      (node (ref "C21") (pin "2") (pinfunction "2_2") (pintype "passive"))
      (node (ref "U8") (pin "3") (pinfunction "VCP_3") (pintype "passive"))
    )
    (net (code "65") (name "Net-(U8-~FAULT)") (class "Default")
      (node (ref "R13") (pin "2") (pintype "passive"))
      (node (ref "U8") (pin "18") (pinfunction "~FAULT_18") (pintype "passive"))
    )
    (net (code "66") (name "Net-(U9-CP1)") (class "Default")
      (node (ref "C27") (pin "2") (pinfunction "2_2") (pintype "passive"))
      (node (ref "U9") (pin "1") (pinfunction "CP1_1") (pintype "passive"))
    )
    (net (code "67") (name "Net-(U9-CP2)") (class "Default")
      (node (ref "C27") (pin "1") (pinfunction "1_1") (pintype "passive"))
      (node (ref "U9") (pin "2") (pinfunction "CP2_2") (pintype "passive"))
    )
    (net (code "68") (name "Net-(U9-ISENA)") (class "Default")
      (node (ref "R20") (pin "2") (pinfunction "2_2") (pintype "passive"))
      (node (ref "U9") (pin "6") (pinfunction "ISENA_6") (pintype "passive"))
    )
    (net (code "69") (name "Net-(U9-ISENB)") (class "Default")
      (node (ref "R19") (pin "2") (pinfunction "2_2") (pintype "passive"))
      (node (ref "U9") (pin "9") (pinfunction "ISENB_9") (pintype "passive"))
    )
    (net (code "70") (name "Net-(U9-VCP)") (class "Default")
      (node (ref "C26") (pin "2") (pinfunction "2_2") (pintype "passive"))
      (node (ref "U9") (pin "3") (pinfunction "VCP_3") (pintype "passive"))
    )
    (net (code "71") (name "Net-(U9-~FAULT)") (class "Default")
      (node (ref "R18") (pin "2") (pintype "passive"))
      (node (ref "U9") (pin "18") (pinfunction "~FAULT_18") (pintype "passive"))
    )
    (net (code "72") (name "VBUS") (class "Default")
      (node (ref "C8") (pin "2") (pinfunction "2_2") (pintype "passive"))
      (node (ref "P1") (pin "1") (pinfunction "VCC_1") (pintype "passive"))
      (node (ref "U4") (pin "16") (pinfunction "VCC_16") (pintype "passive"))
    )
    (net (code "73") (name "VOUT1") (class "Default")
      (node (ref "C20") (pin "2") (pinfunction "2_2") (pintype "passive"))
      (node (ref "R11") (pin "2") (pinfunction "BOT_2") (pintype "passive"))
      (node (ref "U8") (pin "15") (pinfunction "V3P3OUT_15") (pintype "passive"))
    )
    (net (code "74") (name "VOUT2") (class "Default")
      (node (ref "C25") (pin "2") (pinfunction "2_2") (pintype "passive"))
      (node (ref "R16") (pin "2") (pinfunction "BOT_2") (pintype "passive"))
      (node (ref "U9") (pin "15") (pinfunction "V3P3OUT_15") (pintype "passive"))
    )
    (net (code "75") (name "unconnected-(U3-MR-Pad1)") (class "Default")
      (node (ref "U3") (pin "1") (pinfunction "MR_1") (pintype "passive+no_connect"))
    )
    (net (code "76") (name "unconnected-(U3-RST-Pad7)") (class "Default")
      (node (ref "U3") (pin "7") (pinfunction "RST_7") (pintype "passive+no_connect"))
    )
    (net (code "77") (name "unconnected-(U3-WDI-Pad6)") (class "Default")
      (node (ref "U3") (pin "6") (pinfunction "WDI_6") (pintype "passive+no_connect"))
    )
    (net (code "78") (name "unconnected-(U3-WDO-Pad8)") (class "Default")
      (node (ref "U3") (pin "8") (pinfunction "WDO_8") (pintype "passive+no_connect"))
    )
    (net (code "79") (name "unconnected-(U4-CTS#-Pad9)") (class "Default")
      (node (ref "U4") (pin "9") (pinfunction "CTS#_9") (pintype "passive+no_connect"))
    )
    (net (code "80") (name "unconnected-(U4-DCD#-Pad12)") (class "Default")
      (node (ref "U4") (pin "12") (pinfunction "DCD#_12") (pintype "passive+no_connect"))
    )
    (net (code "81") (name "unconnected-(U4-DSR#-Pad10)") (class "Default")
      (node (ref "U4") (pin "10") (pinfunction "DSR#_10") (pintype "passive+no_connect"))
    )
    (net (code "82") (name "unconnected-(U4-DTR#-Pad13)") (class "Default")
      (node (ref "U4") (pin "13") (pinfunction "DTR#_13") (pintype "passive+no_connect"))
    )
    (net (code "83") (name "unconnected-(U4-R232-Pad15)") (class "Default")
      (node (ref "U4") (pin "15") (pinfunction "R232_15") (pintype "passive+no_connect"))
    )
    (net (code "84") (name "unconnected-(U4-RI#-Pad11)") (class "Default")
      (node (ref "U4") (pin "11") (pinfunction "RI#_11") (pintype "passive+no_connect"))
    )
    (net (code "85") (name "unconnected-(U4-RTS#-Pad14)") (class "Default")
      (node (ref "U4") (pin "14") (pinfunction "RTS#_14") (pintype "passive+no_connect"))
    )
    (net (code "86") (name "unconnected-(U4-XI-Pad7)") (class "Default")
      (node (ref "U4") (pin "7") (pinfunction "XI_7") (pintype "passive+no_connect"))
    )
    (net (code "87") (name "unconnected-(U4-XO-Pad8)") (class "Default")
      (node (ref "U4") (pin "8") (pinfunction "XO_8") (pintype "passive+no_connect"))
    )
    (net (code "88") (name "unconnected-(U5-P0_1-Pad22)") (class "Default")
      (node (ref "U5") (pin "22") (pinfunction "P0_1_22") (pintype "passive+no_connect"))
    )
    (net (code "89") (name "unconnected-(U5-P0_4-Pad19)") (class "Default")
      (node (ref "U5") (pin "19") (pinfunction "P0_4_19") (pintype "passive+no_connect"))
    )
    (net (code "90") (name "unconnected-(U5-P0_5-Pad18)") (class "Default")
      (node (ref "U5") (pin "18") (pinfunction "P0_5_18") (pintype "passive+no_connect"))
    )
    (net (code "91") (name "unconnected-(U5-P0_6-Pad17)") (class "Default")
      (node (ref "U5") (pin "17") (pinfunction "P0_6_17") (pintype "passive+no_connect"))
    )
    (net (code "92") (name "unconnected-(U5-P1_0-Pad15)") (class "Default")
      (node (ref "U5") (pin "15") (pinfunction "P1_0_15") (pintype "passive+no_connect"))
    )
    (net (code "93") (name "unconnected-(U5-P1_1-Pad14)") (class "Default")
      (node (ref "U5") (pin "14") (pinfunction "P1_1_14") (pintype "passive+no_connect"))
    )
    (net (code "94") (name "unconnected-(U5-P1_2-Pad13)") (class "Default")
      (node (ref "U5") (pin "13") (pinfunction "P1_2_13") (pintype "passive+no_connect"))
    )
    (net (code "95") (name "unconnected-(U5-P1_3-Pad12)") (class "Default")
      (node (ref "U5") (pin "12") (pinfunction "P1_3_12") (pintype "passive+no_connect"))
    )
    (net (code "96") (name "unconnected-(U5-P1_4-Pad11)") (class "Default")
      (node (ref "U5") (pin "11") (pinfunction "P1_4_11") (pintype "passive+no_connect"))
    )
    (net (code "97") (name "unconnected-(U5-P1_5-Pad10)") (class "Default")
      (node (ref "U5") (pin "10") (pinfunction "P1_5_10") (pintype "passive+no_connect"))
    )
    (net (code "98") (name "unconnected-(U5-P1_6-Pad7)") (class "Default")
      (node (ref "U5") (pin "7") (pinfunction "P1_6_7") (pintype "passive+no_connect"))
    )
    (net (code "99") (name "unconnected-(U5-P1_7-Pad6)") (class "Default")
      (node (ref "U5") (pin "6") (pinfunction "P1_7_6") (pintype "passive+no_connect"))
    )
    (net (code "100") (name "unconnected-(U5-P2_0-Pad5)") (class "Default")
      (node (ref "U5") (pin "5") (pinfunction "P2_0_5") (pintype "passive+no_connect"))
    )
    (net (code "101") (name "unconnected-(U5-P2_1{slash}DD-Pad4)") (class "Default")
      (node (ref "U5") (pin "4") (pinfunction "P2_1/DD_4") (pintype "passive+no_connect"))
    )
    (net (code "102") (name "unconnected-(U5-P2_2{slash}DC-Pad3)") (class "Default")
      (node (ref "U5") (pin "3") (pinfunction "P2_2/DC_3") (pintype "passive+no_connect"))
    )
    (net (code "103") (name "unconnected-(U5-USB_N(SDA)-Pad9)") (class "Default")
      (node (ref "U5") (pin "9") (pinfunction "USB_N(SDA)_9") (pintype "passive+no_connect"))
    )
    (net (code "104") (name "unconnected-(U5-USB_P(SCL)-Pad8)") (class "Default")
      (node (ref "U5") (pin "8") (pinfunction "USB_P(SCL)_8") (pintype "passive+no_connect"))
    )
    (net (code "105") (name "unconnected-(U7A-PB1-Pad19)") (class "Default")
      (node (ref "U7") (pin "19") (pinfunction "PB1_19") (pintype "bidirectional+no_connect"))
    )
    (net (code "106") (name "unconnected-(U7A-PB12-Pad25)") (class "Default")
      (node (ref "U7") (pin "25") (pinfunction "PB12_25") (pintype "bidirectional+no_connect"))
    )
    (net (code "107") (name "unconnected-(U7A-PC13-TAMPER-RTC-Pad2)") (class "Default")
      (node (ref "U7") (pin "2") (pinfunction "PC13-TAMPER-RTC_2") (pintype "bidirectional+no_connect"))
    )
    (net (code "108") (name "unconnected-(U7A-PC14-OSC32_IN-Pad3)") (class "Default")
      (node (ref "U7") (pin "3") (pinfunction "PC14-OSC32_IN_3") (pintype "bidirectional+no_connect"))
    )
    (net (code "109") (name "unconnected-(U7A-PC15-OSC32_OUT-Pad4)") (class "Default")
      (node (ref "U7") (pin "4") (pinfunction "PC15-OSC32_OUT_4") (pintype "bidirectional+no_connect"))
    )
    (net (code "110") (name "unconnected-(U8-DECAY-Pad19)") (class "Default")
      (node (ref "U8") (pin "19") (pinfunction "DECAY_19") (pintype "passive+no_connect"))
    )
    (net (code "111") (name "unconnected-(U8-NC-Pad23)") (class "Default")
      (node (ref "U8") (pin "23") (pinfunction "NC_23") (pintype "passive+no_connect"))
    )
    (net (code "112") (name "unconnected-(U8-~HOME-Pad27)") (class "Default")
      (node (ref "U8") (pin "27") (pinfunction "~HOME_27") (pintype "passive+no_connect"))
    )
    (net (code "113") (name "unconnected-(U9-DECAY-Pad19)") (class "Default")
      (node (ref "U9") (pin "19") (pinfunction "DECAY_19") (pintype "passive+no_connect"))
    )
    (net (code "114") (name "unconnected-(U9-NC-Pad23)") (class "Default")
      (node (ref "U9") (pin "23") (pinfunction "NC_23") (pintype "passive+no_connect"))
    )
    (net (code "115") (name "unconnected-(U9-~HOME-Pad27)") (class "Default")
      (node (ref "U9") (pin "27") (pinfunction "~HOME_27") (pintype "passive+no_connect"))
    )
  )
)
